# SD_CARD.net
KiCad netlist of a schematic drawn in Altium Designer
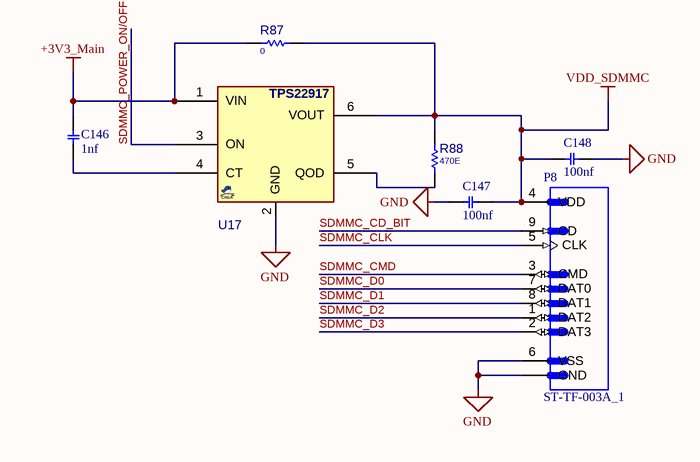
[diagram p0: SD CARD .SchDoc]

(export (version "E")
  (design (tool "Eeschema 10.0.6"))
  (components
    (comp (ref "C146")
      (value "1nf")
      (footprint "C0603")
      (description "Capacitor C SMD 0603")
      (libsource (lib "Capacitor") (part "Capacitor C SMD 0603"))
    )
    (comp (ref "C147")
      (value "100nf")
      (footprint "C0603")
      (description "Capacitor C SMD 0603")
      (libsource (lib "Capacitor") (part "Capacitor C SMD 0603"))
    )
    (comp (ref "C148")
      (value "100nf")
      (footprint "C0603")
      (description "Capacitor C SMD 0603")
      (libsource (lib "Capacitor") (part "Capacitor C SMD 0603"))
    )
    (comp (ref "P8")
      (value "ST-TF-003A_1")
      (footprint "SUNTECH_ST-TF-003A")
      (description "Micro SD Card Socket")
      (fields (field (name "MP") "ST-TF-003A"))
      (libsource (lib "SamacSys") (part "ST-TF-003A_1"))
    )
    (comp (ref "R87")
      (value "0")
      (footprint "R0603")
      (description "RESISTOR, SMD")
      (libsource (lib "passive_smd") (part "RES_SMD_0603"))
    )
    (comp (ref "R88")
      (value "470E")
      (footprint "R0603")
      (description "RESISTOR, SMD")
      (libsource (lib "passive_smd") (part "RES_SMD_0603"))
    )
    (comp (ref "U17")
      (value "TPS22917")
      (footprint "SOT23_6")
      (description "LOAD SW, 2A, 1~5.5v, 80mOhm, SOT23")
      (fields (field (name "MANF") "TI") (field (name "MANF_P#") "TPS22917DBV"))
      (libsource (lib "power_load_switch") (part "TPS22917_SOT23"))
    )
  )
  (nets
    (net (code "1") (name "+3V3_Main") (class "Default")
      (node (ref "C146") (pin "2") (pinfunction "2_2") (pintype "passive"))
      (node (ref "R87") (pin "1") (pinfunction "1_1") (pintype "passive"))
      (node (ref "U17") (pin "1") (pinfunction "VIN_1") (pintype "passive"))
    )
    (net (code "2") (name "/SDMMC_CD_BIT") (class "Default")
      (node (ref "P8") (pin "9") (pinfunction "CD_9") (pintype "input"))
    )
    (net (code "3") (name "/SDMMC_CLK") (class "Default")
      (node (ref "P8") (pin "5") (pinfunction "CLK_5") (pintype "input"))
    )
    (net (code "4") (name "/SDMMC_CMD") (class "Default")
      (node (ref "P8") (pin "3") (pinfunction "CMD_3") (pintype "bidirectional"))
    )
    (net (code "5") (name "/SDMMC_D0") (class "Default")
      (node (ref "P8") (pin "7") (pinfunction "DAT0_7") (pintype "bidirectional"))
    )
    (net (code "6") (name "/SDMMC_D1") (class "Default")
      (node (ref "P8") (pin "8") (pinfunction "DAT1_8") (pintype "bidirectional"))
    )
    (net (code "7") (name "/SDMMC_D2") (class "Default")
      (node (ref "P8") (pin "1") (pinfunction "DAT2_1") (pintype "bidirectional"))
    )
    (net (code "8") (name "/SDMMC_D3") (class "Default")
      (node (ref "P8") (pin "2") (pinfunction "DAT3_2") (pintype "bidirectional"))
    )
    (net (code "9") (name "/SDMMC_POWER_ON{slash}OFF") (class "Default")
      (node (ref "U17") (pin "3") (pinfunction "ON_3") (pintype "passive"))
    )
    (net (code "10") (name "GND") (class "Default")
      (node (ref "C147") (pin "2") (pinfunction "2_2") (pintype "passive"))
      (node (ref "C148") (pin "1") (pinfunction "1_1") (pintype "passive"))
      (node (ref "P8") (pin "6") (pinfunction "VSS_6") (pintype "passive"))
      (node (ref "P8") (pin "G1") (pinfunction "GND_G1") (pintype "passive"))
      (node (ref "U17") (pin "2") (pinfunction "GND_2") (pintype "passive"))
    )
    (net (code "11") (name "Net-(U17-CT)") (class "Default")
      (node (ref "C146") (pin "1") (pinfunction "1_1") (pintype "passive"))
      (node (ref "U17") (pin "4") (pinfunction "CT_4") (pintype "passive"))
    )
    (net (code "12") (name "Net-(U17-QOD)") (class "Default")
      (node (ref "R88") (pin "1") (pinfunction "1_1") (pintype "passive"))
      (node (ref "U17") (pin "5") (pinfunction "QOD_5") (pintype "passive"))
    )
    (net (code "13") (name "VDD_SDMMC") (class "Default")
      (node (ref "C147") (pin "1") (pinfunction "1_1") (pintype "passive"))
      (node (ref "C148") (pin "2") (pinfunction "2_2") (pintype "passive"))
      (node (ref "P8") (pin "4") (pinfunction "VDD_4") (pintype "power_in"))
      (node (ref "R87") (pin "2") (pinfunction "2_2") (pintype "passive"))
      (node (ref "R88") (pin "2") (pinfunction "2_2") (pintype "passive"))
      (node (ref "U17") (pin "6") (pinfunction "VOUT_6") (pintype "passive"))
    )
  )
)
